# LEA6T-Eval-V1_2.net
KiCad netlist of a schematic drawn in EAGLE
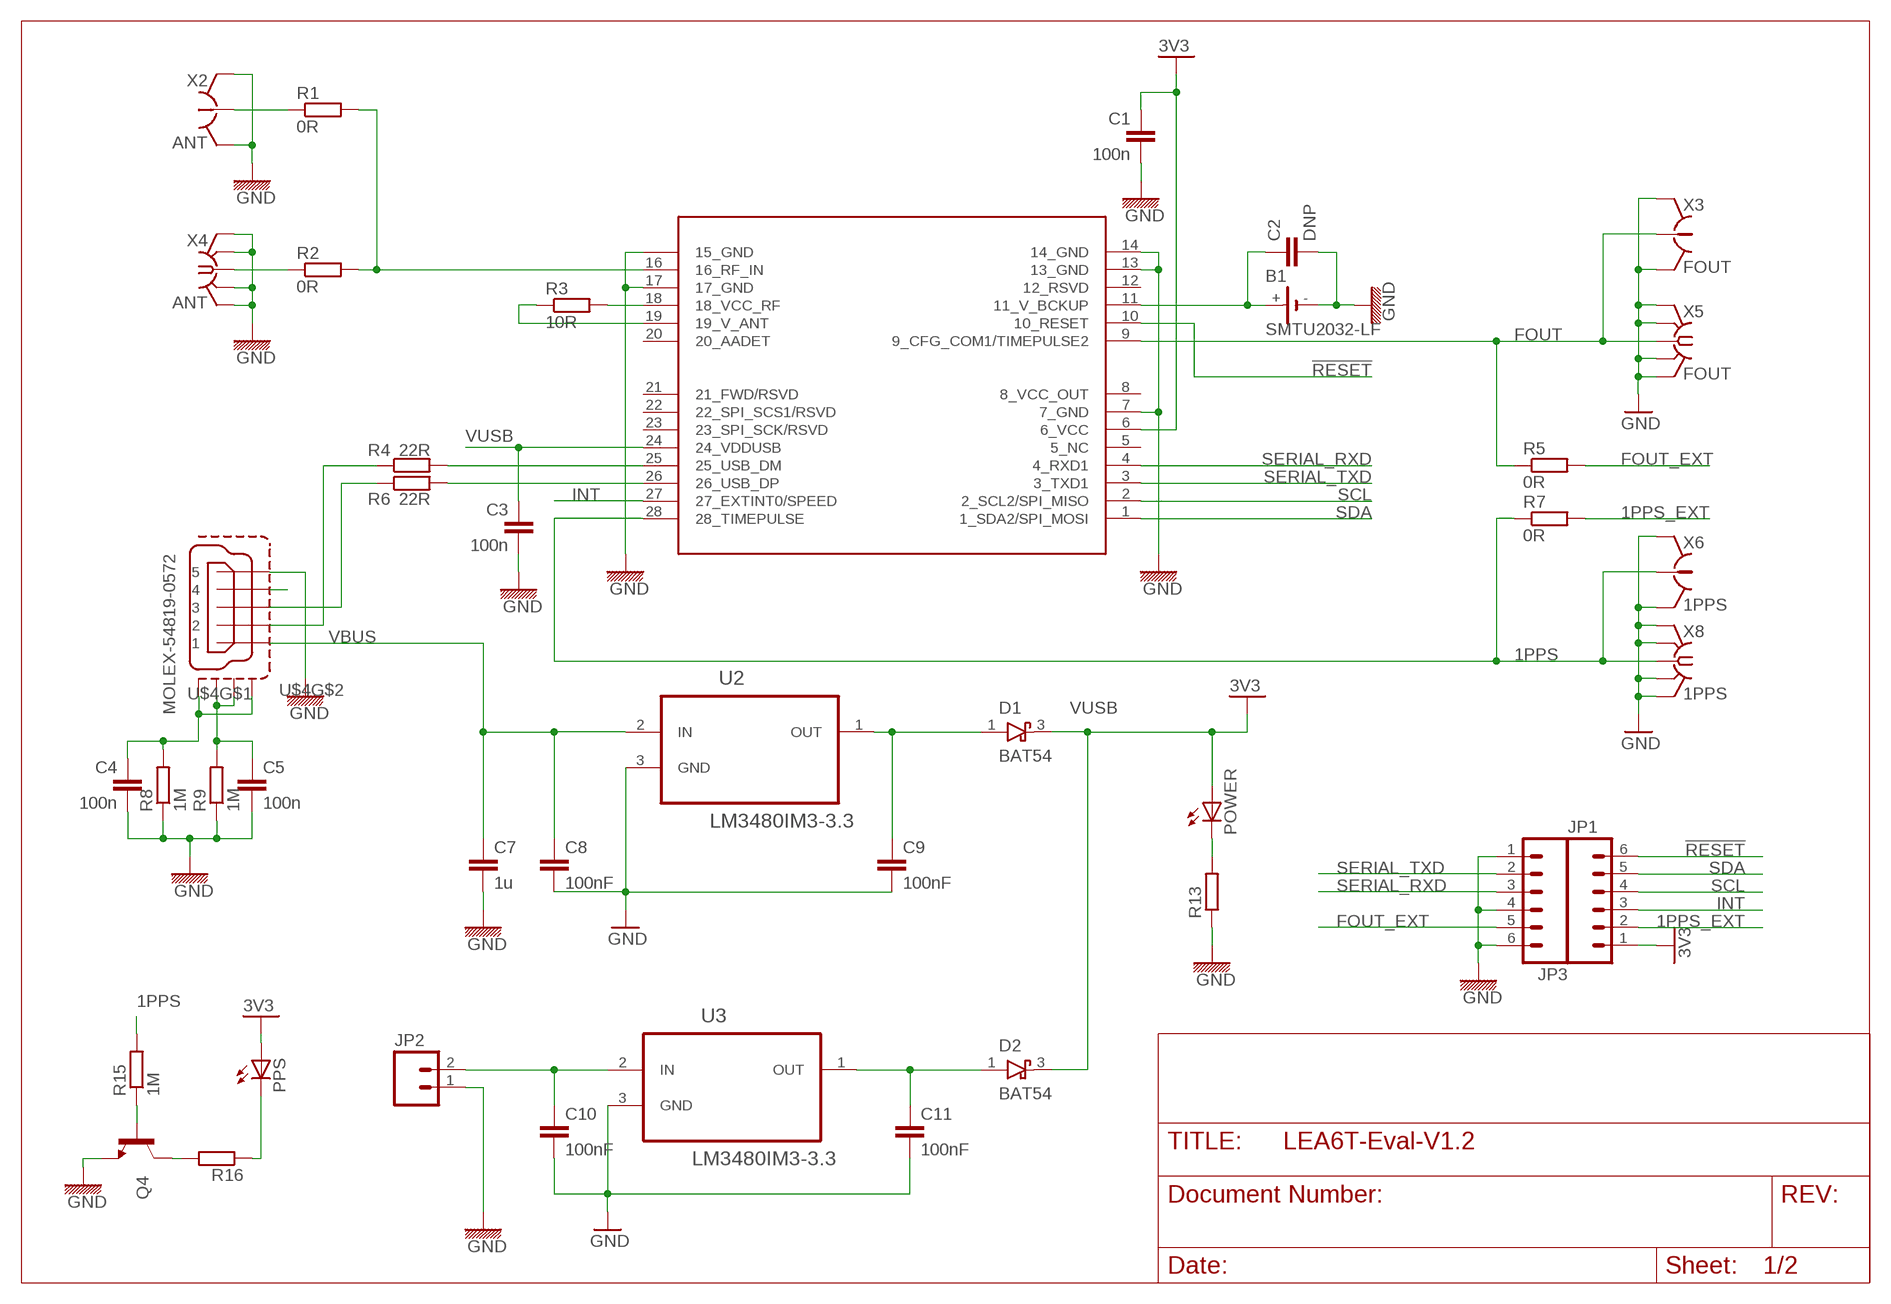
[diagram p0: schematic, sheet 1]
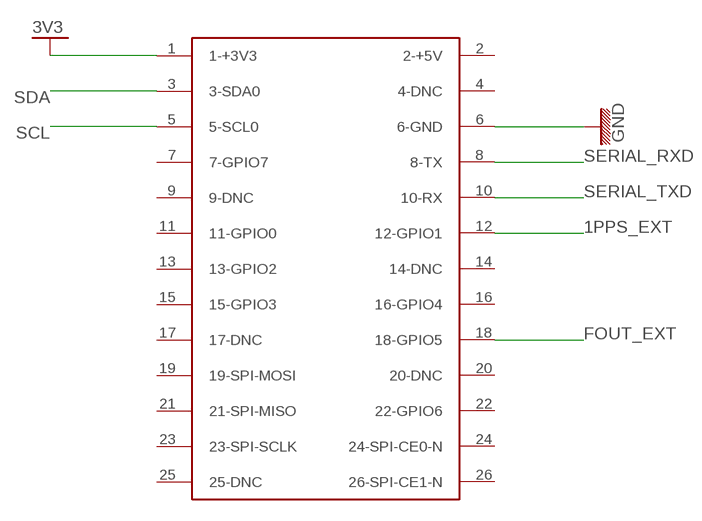
[diagram p1: schematic, sheet 2]

(export (version "E")
  (design (tool "Eeschema 10.0.6"))
  (components
    (comp (ref "B1")
      (value "SMTU2032-LF")
      (footprint "eagle-import:SMTU2032")
      (libsource (lib "eagle-import") (part "BA2032SMD"))
    )
    (comp (ref "C1")
      (value "100n")
      (footprint "eagle-import:0603")
      (libsource (lib "eagle-import") (part "C-EU_0603"))
    )
    (comp (ref "C2")
      (value "DNP")
      (footprint "eagle-import:0603")
      (libsource (lib "eagle-import") (part "C-EU_0603"))
    )
    (comp (ref "C3")
      (value "100n")
      (footprint "eagle-import:0603")
      (libsource (lib "eagle-import") (part "C-EU_0603"))
    )
    (comp (ref "C4")
      (value "100n")
      (footprint "eagle-import:0603")
      (libsource (lib "eagle-import") (part "C-EU_0603"))
    )
    (comp (ref "C5")
      (value "100n")
      (footprint "eagle-import:0603")
      (libsource (lib "eagle-import") (part "C-EU_0603"))
    )
    (comp (ref "C7")
      (value "1u")
      (footprint "eagle-import:0603")
      (libsource (lib "eagle-import") (part "C-EU_0603"))
    )
    (comp (ref "C8")
      (value "100nF")
      (footprint "eagle-import:0603-CAP")
      (libsource (lib "eagle-import") (part "CAP0603-CAP"))
    )
    (comp (ref "C9")
      (value "100nF")
      (footprint "eagle-import:0603-CAP")
      (libsource (lib "eagle-import") (part "CAP0603-CAP"))
    )
    (comp (ref "C10")
      (value "100nF")
      (footprint "eagle-import:0603-CAP")
      (libsource (lib "eagle-import") (part "CAP0603-CAP"))
    )
    (comp (ref "C11")
      (value "100nF")
      (footprint "eagle-import:0603-CAP")
      (libsource (lib "eagle-import") (part "CAP0603-CAP"))
    )
    (comp (ref "D1")
      (value "BAT54")
      (footprint "eagle-import:SOT23")
      (libsource (lib "eagle-import") (part "D_SCHOTTKY_SOT23"))
    )
    (comp (ref "D2")
      (value "BAT54")
      (footprint "eagle-import:SOT23")
      (libsource (lib "eagle-import") (part "D_SCHOTTKY_SOT23"))
    )
    (comp (ref "JP1")
      (value "M06SIP")
      (footprint "eagle-import:1X06")
      (libsource (lib "eagle-import") (part "M06SIP"))
    )
    (comp (ref "JP2")
      (value "M02PTH")
      (footprint "eagle-import:1X02")
      (libsource (lib "eagle-import") (part "M02PTH"))
    )
    (comp (ref "JP3")
      (value "M06SIP")
      (footprint "eagle-import:1X06")
      (libsource (lib "eagle-import") (part "M06SIP"))
    )
    (comp (ref "POWER")
      (value "LEDSML0603")
      (footprint "eagle-import:SML0603")
      (libsource (lib "eagle-import") (part "LEDSML0603"))
    )
    (comp (ref "PPS")
      (value "LEDSML0603")
      (footprint "eagle-import:SML0603")
      (libsource (lib "eagle-import") (part "LEDSML0603"))
    )
    (comp (ref "Q4")
      (value "TRANSISTOR_NPNSOT23")
      (footprint "eagle-import:SOT23")
      (libsource (lib "eagle-import") (part "TRANSISTOR_NPNSOT23"))
    )
    (comp (ref "R1")
      (value "0R")
      (footprint "eagle-import:0603")
      (libsource (lib "eagle-import") (part "R-EU_0603"))
    )
    (comp (ref "R2")
      (value "0R")
      (footprint "eagle-import:0603")
      (libsource (lib "eagle-import") (part "R-EU_0603"))
    )
    (comp (ref "R3")
      (value "10R")
      (footprint "eagle-import:0603")
      (libsource (lib "eagle-import") (part "R-EU_0603"))
    )
    (comp (ref "R4")
      (value "22R")
      (footprint "eagle-import:0603")
      (libsource (lib "eagle-import") (part "R-EU_0603"))
    )
    (comp (ref "R5")
      (value "0R")
      (footprint "eagle-import:0603")
      (libsource (lib "eagle-import") (part "R-EU_0603"))
    )
    (comp (ref "R6")
      (value "22R")
      (footprint "eagle-import:0603")
      (libsource (lib "eagle-import") (part "R-EU_0603"))
    )
    (comp (ref "R7")
      (value "0R")
      (footprint "eagle-import:0603")
      (libsource (lib "eagle-import") (part "R-EU_0603"))
    )
    (comp (ref "R8")
      (value "1M")
      (footprint "eagle-import:0603")
      (libsource (lib "eagle-import") (part "R-EU_0603"))
    )
    (comp (ref "R9")
      (value "1M")
      (footprint "eagle-import:0603")
      (libsource (lib "eagle-import") (part "R-EU_0603"))
    )
    (comp (ref "R13")
      (value "R-EU_0603")
      (footprint "eagle-import:0603")
      (libsource (lib "eagle-import") (part "R-EU_0603"))
    )
    (comp (ref "R15")
      (value "1M")
      (footprint "eagle-import:0603")
      (libsource (lib "eagle-import") (part "R-EU_0603"))
    )
    (comp (ref "R16")
      (value "R-EU_0603")
      (footprint "eagle-import:0603")
      (libsource (lib "eagle-import") (part "R-EU_0603"))
    )
    (comp (ref "U$4")
      (value "MOLEX-54819-0572")
      (footprint "eagle-import:MOLEX-54819-0572")
      (libsource (lib "eagle-import") (part "MOLEX-54819-0572"))
    )
    (comp (ref "U1")
      (value "UBLOX_LEA-6")
      (footprint "eagle-import:UBLOX_LEA-6T")
      (libsource (lib "eagle-import") (part "UBLOX_LEA-6"))
    )
    (comp (ref "U2")
      (value "LM3480IM3-3.3")
      (footprint "eagle-import:SOT95P251X112-3N")
      (libsource (lib "eagle-import") (part "LM3480IM3-3.3"))
    )
    (comp (ref "U3")
      (value "LM3480IM3-3.3")
      (footprint "eagle-import:SOT95P251X112-3N")
      (libsource (lib "eagle-import") (part "LM3480IM3-3.3"))
    )
    (comp (ref "X2")
      (value "ANT")
      (footprint "eagle-import:HRS_UFL")
      (libsource (lib "eagle-import") (part "HRS_UFL"))
    )
    (comp (ref "X3")
      (value "FOUT")
      (footprint "eagle-import:HRS_UFL")
      (libsource (lib "eagle-import") (part "HRS_UFL"))
    )
    (comp (ref "X4")
      (value "ANT")
      (footprint "eagle-import:SMA-F-S-EDGE")
      (libsource (lib "eagle-import") (part "SMA-F-S-EDGE"))
    )
    (comp (ref "X5")
      (value "FOUT")
      (footprint "eagle-import:SMA-F-S-EDGE")
      (libsource (lib "eagle-import") (part "SMA-F-S-EDGE"))
    )
    (comp (ref "X6")
      (value "1PPS")
      (footprint "eagle-import:HRS_UFL")
      (libsource (lib "eagle-import") (part "HRS_UFL"))
    )
    (comp (ref "X8")
      (value "1PPS")
      (footprint "eagle-import:SMA-F-S-EDGE")
      (libsource (lib "eagle-import") (part "SMA-F-S-EDGE"))
    )
    (comp (ref "U$30")
      (value "RASPBERRY-PINOCRAP")
      (footprint "eagle-import:RASPBERRY-PI_NOCONNS")
      (libsource (lib "eagle-import") (part "RASPBERRY-PINOCRAP"))
    )
  )
  (nets
    (net (code "1") (name "1PPS") (class "Default")
      (node (ref "R15") (pin "2") (pinfunction "2_2") (pintype "passive"))
      (node (ref "R7") (pin "1") (pinfunction "1_1") (pintype "passive"))
      (node (ref "U1") (pin "28") (pinfunction "28_TIMEPULSE_28") (pintype "bidirectional"))
      (node (ref "X6") (pin "SIG") (pinfunction "1_SIG") (pintype "passive"))
      (node (ref "X8") (pin "C") (pinfunction "1_C") (pintype "passive"))
    )
    (net (code "2") (name "1PPS_EXT") (class "Default")
      (node (ref "JP1") (pin "2") (pinfunction "2_2") (pintype "passive"))
      (node (ref "R7") (pin "2") (pinfunction "2_2") (pintype "passive"))
      (node (ref "U$30") (pin "12") (pinfunction "12-GPIO1_12") (pintype "bidirectional"))
    )
    (net (code "3") (name "3V3") (class "Default")
      (node (ref "C1") (pin "1") (pinfunction "1_1") (pintype "passive"))
      (node (ref "D1") (pin "3") (pinfunction "C_3") (pintype "passive"))
      (node (ref "D2") (pin "3") (pinfunction "C_3") (pintype "passive"))
      (node (ref "JP1") (pin "1") (pinfunction "1_1") (pintype "passive"))
      (node (ref "POWER") (pin "A") (pinfunction "A_A") (pintype "passive"))
      (node (ref "PPS") (pin "A") (pinfunction "A_A") (pintype "passive"))
      (node (ref "U$30") (pin "1") (pinfunction "1-+3V3_1") (pintype "bidirectional"))
      (node (ref "U1") (pin "6") (pinfunction "6_VCC_6") (pintype "bidirectional"))
    )
    (net (code "4") (name "FOUT") (class "Default")
      (node (ref "R5") (pin "1") (pinfunction "1_1") (pintype "passive"))
      (node (ref "U1") (pin "9") (pinfunction "9_CFG_COM1/TIMEPULSE2_9") (pintype "bidirectional"))
      (node (ref "X3") (pin "SIG") (pinfunction "1_SIG") (pintype "passive"))
      (node (ref "X5") (pin "C") (pinfunction "1_C") (pintype "passive"))
    )
    (net (code "5") (name "FOUT_EXT") (class "Default")
      (node (ref "JP3") (pin "5") (pinfunction "5_5") (pintype "passive"))
      (node (ref "R5") (pin "2") (pinfunction "2_2") (pintype "passive"))
      (node (ref "U$30") (pin "18") (pinfunction "18-GPIO5_18") (pintype "bidirectional"))
    )
    (net (code "6") (name "GND") (class "Default")
      (node (ref "B1") (pin "-") (pinfunction "-_-") (pintype "passive"))
      (node (ref "C1") (pin "2") (pinfunction "2_2") (pintype "passive"))
      (node (ref "C10") (pin "2") (pinfunction "2_2") (pintype "passive"))
      (node (ref "C11") (pin "2") (pinfunction "2_2") (pintype "passive"))
      (node (ref "C2") (pin "2") (pinfunction "2_2") (pintype "passive"))
      (node (ref "C3") (pin "2") (pinfunction "2_2") (pintype "passive"))
      (node (ref "C4") (pin "2") (pinfunction "2_2") (pintype "passive"))
      (node (ref "C5") (pin "2") (pinfunction "2_2") (pintype "passive"))
      (node (ref "C7") (pin "2") (pinfunction "2_2") (pintype "passive"))
      (node (ref "C8") (pin "2") (pinfunction "2_2") (pintype "passive"))
      (node (ref "C9") (pin "2") (pinfunction "2_2") (pintype "passive"))
      (node (ref "JP2") (pin "1") (pinfunction "1_1") (pintype "passive"))
      (node (ref "JP3") (pin "1") (pinfunction "1_1") (pintype "passive"))
      (node (ref "JP3") (pin "4") (pinfunction "4_4") (pintype "passive"))
      (node (ref "JP3") (pin "6") (pinfunction "6_6") (pintype "passive"))
      (node (ref "Q4") (pin "2") (pinfunction "E_2") (pintype "passive"))
      (node (ref "R13") (pin "1") (pinfunction "1_1") (pintype "passive"))
      (node (ref "R8") (pin "1") (pinfunction "1_1") (pintype "passive"))
      (node (ref "R9") (pin "1") (pinfunction "1_1") (pintype "passive"))
      (node (ref "U$30") (pin "6") (pinfunction "6-GND_6") (pintype "bidirectional"))
      (node (ref "U$4") (pin "5") (pinfunction "5_5") (pintype "input"))
      (node (ref "U1") (pin "13") (pinfunction "13_GND_13") (pintype "bidirectional"))
      (node (ref "U1") (pin "14") (pinfunction "14_GND_14") (pintype "bidirectional"))
      (node (ref "U1") (pin "15") (pinfunction "15_GND_15") (pintype "bidirectional"))
      (node (ref "U1") (pin "17") (pinfunction "17_GND_17") (pintype "bidirectional"))
      (node (ref "U1") (pin "7") (pinfunction "7_GND_7") (pintype "bidirectional"))
      (node (ref "U2") (pin "3") (pinfunction "GND_3") (pintype "passive"))
      (node (ref "U3") (pin "3") (pinfunction "GND_3") (pintype "passive"))
      (node (ref "X2") (pin "GND@1") (pinfunction "GND_GND@1") (pintype "power_in"))
      (node (ref "X2") (pin "GND@2") (pinfunction "GND_GND@2") (pintype "power_in"))
      (node (ref "X3") (pin "GND@1") (pinfunction "GND_GND@1") (pintype "power_in"))
      (node (ref "X3") (pin "GND@2") (pinfunction "GND_GND@2") (pintype "power_in"))
      (node (ref "X4") (pin "BG1") (pinfunction "GND_BG1") (pintype "power_in"))
      (node (ref "X4") (pin "BG2") (pinfunction "GND_BG2") (pintype "power_in"))
      (node (ref "X4") (pin "TG1") (pinfunction "GND_TG1") (pintype "power_in"))
      (node (ref "X4") (pin "TG2") (pinfunction "GND_TG2") (pintype "power_in"))
      (node (ref "X5") (pin "BG1") (pinfunction "GND_BG1") (pintype "power_in"))
      (node (ref "X5") (pin "BG2") (pinfunction "GND_BG2") (pintype "power_in"))
      (node (ref "X5") (pin "TG1") (pinfunction "GND_TG1") (pintype "power_in"))
      (node (ref "X5") (pin "TG2") (pinfunction "GND_TG2") (pintype "power_in"))
      (node (ref "X6") (pin "GND@1") (pinfunction "GND_GND@1") (pintype "power_in"))
      (node (ref "X6") (pin "GND@2") (pinfunction "GND_GND@2") (pintype "power_in"))
      (node (ref "X8") (pin "BG1") (pinfunction "GND_BG1") (pintype "power_in"))
      (node (ref "X8") (pin "BG2") (pinfunction "GND_BG2") (pintype "power_in"))
      (node (ref "X8") (pin "TG1") (pinfunction "GND_TG1") (pintype "power_in"))
      (node (ref "X8") (pin "TG2") (pinfunction "GND_TG2") (pintype "power_in"))
    )
    (net (code "7") (name "INT") (class "Default")
      (node (ref "JP1") (pin "3") (pinfunction "3_3") (pintype "passive"))
      (node (ref "U1") (pin "27") (pinfunction "27_EXTINT0/SPEED_27") (pintype "bidirectional"))
    )
    (net (code "8") (name "Net-(D2-A)") (class "Default")
      (node (ref "C11") (pin "1") (pinfunction "1_1") (pintype "passive"))
      (node (ref "D2") (pin "1") (pinfunction "A_1") (pintype "passive"))
      (node (ref "U3") (pin "1") (pinfunction "OUT_1") (pintype "output"))
    )
    (net (code "9") (name "Net-(POWER-PadC)") (class "Default")
      (node (ref "POWER") (pin "C") (pinfunction "C_C") (pintype "passive"))
      (node (ref "R13") (pin "2") (pinfunction "2_2") (pintype "passive"))
    )
    (net (code "10") (name "Net-(PPS-PadC)") (class "Default")
      (node (ref "PPS") (pin "C") (pinfunction "C_C") (pintype "passive"))
      (node (ref "R16") (pin "1") (pinfunction "1_1") (pintype "passive"))
    )
    (net (code "11") (name "Net-(Q4-B)") (class "Default")
      (node (ref "Q4") (pin "1") (pinfunction "B_1") (pintype "passive"))
      (node (ref "R15") (pin "1") (pinfunction "1_1") (pintype "passive"))
    )
    (net (code "12") (name "Net-(Q4-C)") (class "Default")
      (node (ref "Q4") (pin "3") (pinfunction "C_3") (pintype "passive"))
      (node (ref "R16") (pin "2") (pinfunction "2_2") (pintype "passive"))
    )
    (net (code "13") (name "Net-(R4-Pad1)") (class "Default")
      (node (ref "R4") (pin "1") (pinfunction "1_1") (pintype "passive"))
      (node (ref "U$4") (pin "2") (pinfunction "2_2") (pintype "input"))
    )
    (net (code "14") (name "Net-(R6-Pad1)") (class "Default")
      (node (ref "R6") (pin "1") (pinfunction "1_1") (pintype "passive"))
      (node (ref "U$4") (pin "3") (pinfunction "3_3") (pintype "input"))
    )
    (net (code "15") (name "Net-(U$4B-S1)") (class "Default")
      (node (ref "C4") (pin "1") (pinfunction "1_1") (pintype "passive"))
      (node (ref "R8") (pin "2") (pinfunction "2_2") (pintype "passive"))
      (node (ref "U$4") (pin "M1") (pinfunction "S1_M1") (pintype "passive"))
      (node (ref "U$4") (pin "M4") (pinfunction "S4_M4") (pintype "passive"))
    )
    (net (code "16") (name "Net-(U$4B-S2)") (class "Default")
      (node (ref "C5") (pin "1") (pinfunction "1_1") (pintype "passive"))
      (node (ref "R9") (pin "2") (pinfunction "2_2") (pintype "passive"))
      (node (ref "U$4") (pin "M2") (pinfunction "S2_M2") (pintype "passive"))
      (node (ref "U$4") (pin "M3") (pinfunction "S3_M3") (pintype "passive"))
    )
    (net (code "17") (name "Net-(U1-11_V_BCKUP)") (class "Default")
      (node (ref "B1") (pin "+") (pinfunction "+_+") (pintype "passive"))
      (node (ref "C2") (pin "1") (pinfunction "1_1") (pintype "passive"))
      (node (ref "U1") (pin "11") (pinfunction "11_V_BCKUP_11") (pintype "bidirectional"))
    )
    (net (code "18") (name "Net-(U1-16_RF_IN)") (class "Default")
      (node (ref "R1") (pin "2") (pinfunction "2_2") (pintype "passive"))
      (node (ref "R2") (pin "2") (pinfunction "2_2") (pintype "passive"))
      (node (ref "U1") (pin "16") (pinfunction "16_RF_IN_16") (pintype "bidirectional"))
    )
    (net (code "19") (name "Net-(U1-18_VCC_RF)") (class "Default")
      (node (ref "R3") (pin "2") (pinfunction "2_2") (pintype "passive"))
      (node (ref "U1") (pin "18") (pinfunction "18_VCC_RF_18") (pintype "bidirectional"))
    )
    (net (code "20") (name "Net-(U1-19_V_ANT)") (class "Default")
      (node (ref "R3") (pin "1") (pinfunction "1_1") (pintype "passive"))
      (node (ref "U1") (pin "19") (pinfunction "19_V_ANT_19") (pintype "bidirectional"))
    )
    (net (code "21") (name "Net-(U1-25_USB_DM)") (class "Default")
      (node (ref "R4") (pin "2") (pinfunction "2_2") (pintype "passive"))
      (node (ref "U1") (pin "25") (pinfunction "25_USB_DM_25") (pintype "bidirectional"))
    )
    (net (code "22") (name "Net-(U1-26_USB_DP)") (class "Default")
      (node (ref "R6") (pin "2") (pinfunction "2_2") (pintype "passive"))
      (node (ref "U1") (pin "26") (pinfunction "26_USB_DP_26") (pintype "bidirectional"))
    )
    (net (code "23") (name "Net-(U3-IN)") (class "Default")
      (node (ref "C10") (pin "1") (pinfunction "1_1") (pintype "passive"))
      (node (ref "JP2") (pin "2") (pinfunction "2_2") (pintype "passive"))
      (node (ref "U3") (pin "2") (pinfunction "IN_2") (pintype "power_in"))
    )
    (net (code "24") (name "Net-(X2-1)") (class "Default")
      (node (ref "R1") (pin "1") (pinfunction "1_1") (pintype "passive"))
      (node (ref "X2") (pin "SIG") (pinfunction "1_SIG") (pintype "passive"))
    )
    (net (code "25") (name "Net-(X4-1)") (class "Default")
      (node (ref "R2") (pin "1") (pinfunction "1_1") (pintype "passive"))
      (node (ref "X4") (pin "C") (pinfunction "1_C") (pintype "passive"))
    )
    (net (code "26") (name "SCL") (class "Default")
      (node (ref "JP1") (pin "4") (pinfunction "4_4") (pintype "passive"))
      (node (ref "U$30") (pin "5") (pinfunction "5-SCL0_5") (pintype "bidirectional"))
      (node (ref "U1") (pin "2") (pinfunction "2_SCL2/SPI_MISO_2") (pintype "bidirectional"))
    )
    (net (code "27") (name "SDA") (class "Default")
      (node (ref "JP1") (pin "5") (pinfunction "5_5") (pintype "passive"))
      (node (ref "U$30") (pin "3") (pinfunction "3-SDA0_3") (pintype "bidirectional"))
      (node (ref "U1") (pin "1") (pinfunction "1_SDA2/SPI_MOSI_1") (pintype "bidirectional"))
    )
    (net (code "28") (name "SERIAL_RXD") (class "Default")
      (node (ref "JP3") (pin "3") (pinfunction "3_3") (pintype "passive"))
      (node (ref "U$30") (pin "8") (pinfunction "8-TX_8") (pintype "bidirectional"))
      (node (ref "U1") (pin "4") (pinfunction "4_RXD1_4") (pintype "bidirectional"))
    )
    (net (code "29") (name "SERIAL_TXD") (class "Default")
      (node (ref "JP3") (pin "2") (pinfunction "2_2") (pintype "passive"))
      (node (ref "U$30") (pin "10") (pinfunction "10-RX_10") (pintype "bidirectional"))
      (node (ref "U1") (pin "3") (pinfunction "3_TXD1_3") (pintype "bidirectional"))
    )
    (net (code "30") (name "VBUS") (class "Default")
      (node (ref "C7") (pin "1") (pinfunction "1_1") (pintype "passive"))
      (node (ref "C8") (pin "1") (pinfunction "1_1") (pintype "passive"))
      (node (ref "U$4") (pin "1") (pinfunction "1_1") (pintype "input"))
      (node (ref "U2") (pin "2") (pinfunction "IN_2") (pintype "power_in"))
    )
    (net (code "31") (name "VUSB") (class "Default")
      (node (ref "C3") (pin "1") (pinfunction "1_1") (pintype "passive"))
      (node (ref "C9") (pin "1") (pinfunction "1_1") (pintype "passive"))
      (node (ref "D1") (pin "1") (pinfunction "A_1") (pintype "passive"))
      (node (ref "U1") (pin "24") (pinfunction "24_VDDUSB_24") (pintype "bidirectional"))
      (node (ref "U2") (pin "1") (pinfunction "OUT_1") (pintype "output"))
    )
    (net (code "32") (name "unconnected-(U$4-Pad4)") (class "Default")
      (node (ref "U$4") (pin "4") (pinfunction "4_4") (pintype "input"))
    )
    (net (code "33") (name "unconnected-(U$30-2-+5V-Pad2)") (class "Default")
      (node (ref "U$30") (pin "2") (pinfunction "2-+5V_2") (pintype "bidirectional"))
    )
    (net (code "34") (name "unconnected-(U$30-4-DNC-Pad4)") (class "Default")
      (node (ref "U$30") (pin "4") (pinfunction "4-DNC_4") (pintype "bidirectional"))
    )
    (net (code "35") (name "unconnected-(U$30-7-GPIO7-Pad7)") (class "Default")
      (node (ref "U$30") (pin "7") (pinfunction "7-GPIO7_7") (pintype "bidirectional"))
    )
    (net (code "36") (name "unconnected-(U$30-9-DNC-Pad9)") (class "Default")
      (node (ref "U$30") (pin "9") (pinfunction "9-DNC_9") (pintype "bidirectional"))
    )
    (net (code "37") (name "unconnected-(U$30-11-GPIO0-Pad11)") (class "Default")
      (node (ref "U$30") (pin "11") (pinfunction "11-GPIO0_11") (pintype "bidirectional"))
    )
    (net (code "38") (name "unconnected-(U$30-13-GPIO2-Pad13)") (class "Default")
      (node (ref "U$30") (pin "13") (pinfunction "13-GPIO2_13") (pintype "bidirectional"))
    )
    (net (code "39") (name "unconnected-(U$30-14-DNC-Pad14)") (class "Default")
      (node (ref "U$30") (pin "14") (pinfunction "14-DNC_14") (pintype "bidirectional"))
    )
    (net (code "40") (name "unconnected-(U$30-15-GPIO3-Pad15)") (class "Default")
      (node (ref "U$30") (pin "15") (pinfunction "15-GPIO3_15") (pintype "bidirectional"))
    )
    (net (code "41") (name "unconnected-(U$30-16-GPIO4-Pad16)") (class "Default")
      (node (ref "U$30") (pin "16") (pinfunction "16-GPIO4_16") (pintype "bidirectional"))
    )
    (net (code "42") (name "unconnected-(U$30-17-DNC-Pad17)") (class "Default")
      (node (ref "U$30") (pin "17") (pinfunction "17-DNC_17") (pintype "bidirectional"))
    )
    (net (code "43") (name "unconnected-(U$30-19-SPI-MOSI-Pad19)") (class "Default")
      (node (ref "U$30") (pin "19") (pinfunction "19-SPI-MOSI_19") (pintype "bidirectional"))
    )
    (net (code "44") (name "unconnected-(U$30-20-DNC-Pad20)") (class "Default")
      (node (ref "U$30") (pin "20") (pinfunction "20-DNC_20") (pintype "bidirectional"))
    )
    (net (code "45") (name "unconnected-(U$30-21-SPI-MISO-Pad21)") (class "Default")
      (node (ref "U$30") (pin "21") (pinfunction "21-SPI-MISO_21") (pintype "bidirectional"))
    )
    (net (code "46") (name "unconnected-(U$30-22-GPIO6-Pad22)") (class "Default")
      (node (ref "U$30") (pin "22") (pinfunction "22-GPIO6_22") (pintype "bidirectional"))
    )
    (net (code "47") (name "unconnected-(U$30-23-SPI-SCLK-Pad23)") (class "Default")
      (node (ref "U$30") (pin "23") (pinfunction "23-SPI-SCLK_23") (pintype "bidirectional"))
    )
    (net (code "48") (name "unconnected-(U$30-24-SPI-CE0-N-Pad24)") (class "Default")
      (node (ref "U$30") (pin "24") (pinfunction "24-SPI-CE0-N_24") (pintype "bidirectional"))
    )
    (net (code "49") (name "unconnected-(U$30-25-DNC-Pad25)") (class "Default")
      (node (ref "U$30") (pin "25") (pinfunction "25-DNC_25") (pintype "bidirectional"))
    )
    (net (code "50") (name "unconnected-(U$30-26-SPI-CE1-N-Pad26)") (class "Default")
      (node (ref "U$30") (pin "26") (pinfunction "26-SPI-CE1-N_26") (pintype "bidirectional"))
    )
    (net (code "51") (name "unconnected-(U1-5_NC-Pad5)") (class "Default")
      (node (ref "U1") (pin "5") (pinfunction "5_NC_5") (pintype "bidirectional"))
    )
    (net (code "52") (name "unconnected-(U1-8_VCC_OUT-Pad8)") (class "Default")
      (node (ref "U1") (pin "8") (pinfunction "8_VCC_OUT_8") (pintype "bidirectional"))
    )
    (net (code "53") (name "unconnected-(U1-12_RSVD-Pad12)") (class "Default")
      (node (ref "U1") (pin "12") (pinfunction "12_RSVD_12") (pintype "bidirectional"))
    )
    (net (code "54") (name "unconnected-(U1-20_AADET-Pad20)") (class "Default")
      (node (ref "U1") (pin "20") (pinfunction "20_AADET_20") (pintype "bidirectional"))
    )
    (net (code "55") (name "unconnected-(U1-21_FWD{slash}RSVD-Pad21)") (class "Default")
      (node (ref "U1") (pin "21") (pinfunction "21_FWD/RSVD_21") (pintype "bidirectional"))
    )
    (net (code "56") (name "unconnected-(U1-22_SPI_SCS1{slash}RSVD-Pad22)") (class "Default")
      (node (ref "U1") (pin "22") (pinfunction "22_SPI_SCS1/RSVD_22") (pintype "bidirectional"))
    )
    (net (code "57") (name "unconnected-(U1-23_SPI_SCK{slash}RSVD-Pad23)") (class "Default")
      (node (ref "U1") (pin "23") (pinfunction "23_SPI_SCK/RSVD_23") (pintype "bidirectional"))
    )
    (net (code "58") (name "~{RESET}") (class "Default")
      (node (ref "JP1") (pin "6") (pinfunction "6_6") (pintype "passive"))
      (node (ref "U1") (pin "10") (pinfunction "10_RESET_10") (pintype "bidirectional"))
    )
  )
)
